# electric_fence.net
KiCad netlist of a schematic drawn in EAGLE
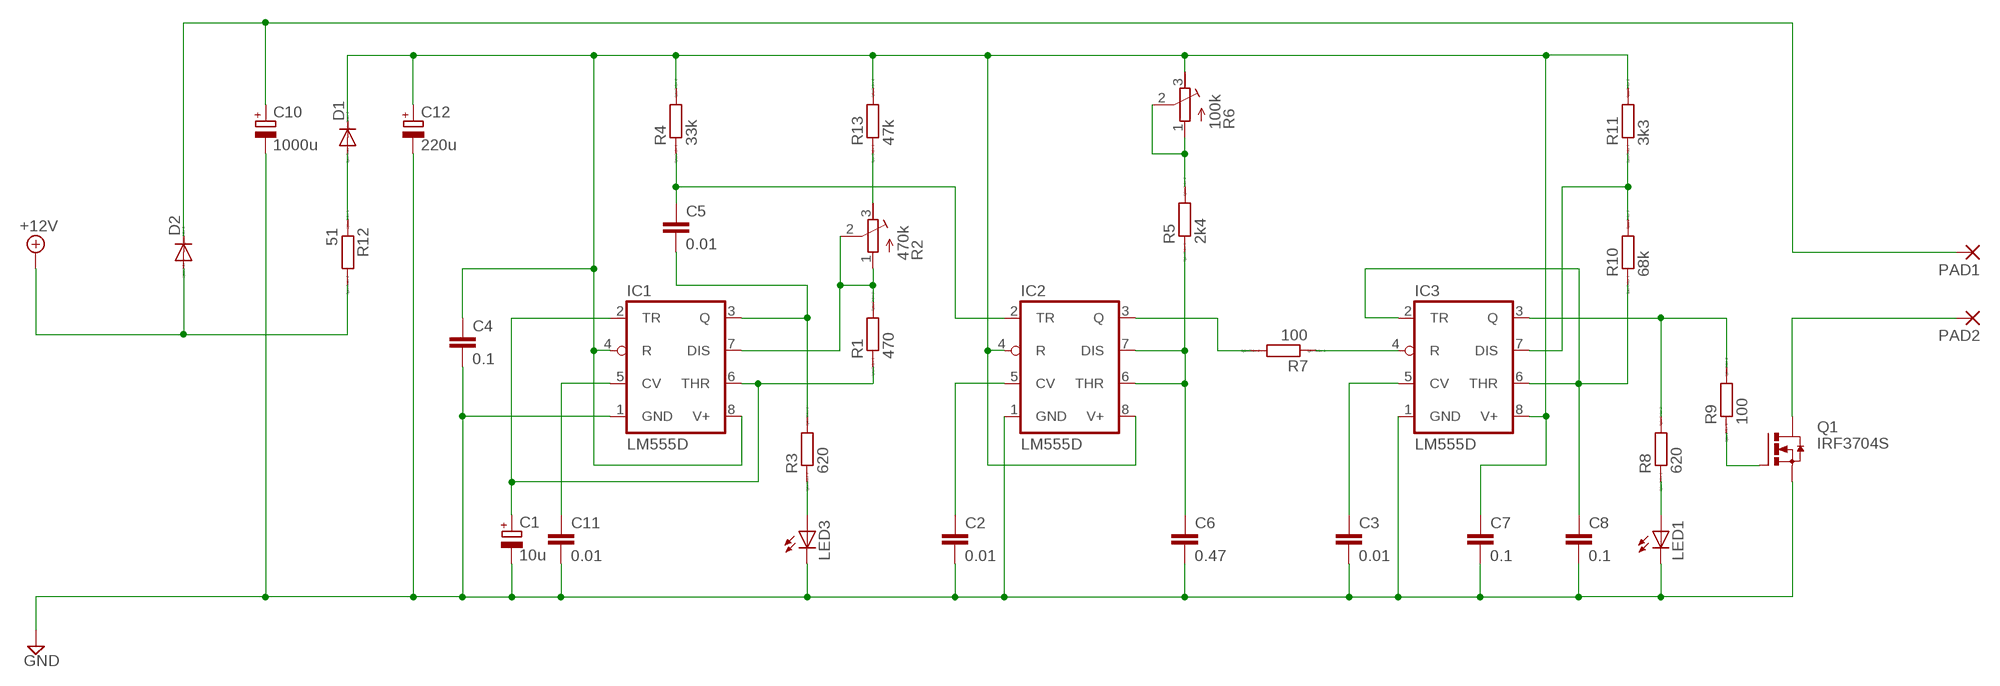
[diagram p0: schematic, sheet 1]

(export (version "E")
  (design (tool "Eeschema 10.0.6"))
  (components
    (comp (ref "C1")
      (value "10u")
      (footprint "eagle-import:E2-4")
      (libsource (lib "eagle-import") (part "CPOL-EUE2-4"))
    )
    (comp (ref "C2")
      (value "0.01")
      (footprint "eagle-import:C0402")
      (libsource (lib "eagle-import") (part "C-EUC0402"))
    )
    (comp (ref "C3")
      (value "0.01")
      (footprint "eagle-import:C0402")
      (libsource (lib "eagle-import") (part "C-EUC0402"))
    )
    (comp (ref "C4")
      (value "0.1")
      (footprint "eagle-import:C0402")
      (libsource (lib "eagle-import") (part "C-EUC0402"))
    )
    (comp (ref "C5")
      (value "0.01")
      (footprint "eagle-import:C0402")
      (libsource (lib "eagle-import") (part "C-EUC0402"))
    )
    (comp (ref "C6")
      (value "0.47")
      (footprint "eagle-import:C0402")
      (libsource (lib "eagle-import") (part "C-EUC0402"))
    )
    (comp (ref "C7")
      (value "0.1")
      (footprint "eagle-import:C0402")
      (libsource (lib "eagle-import") (part "C-EUC0402"))
    )
    (comp (ref "C8")
      (value "0.1")
      (footprint "eagle-import:C0402")
      (libsource (lib "eagle-import") (part "C-EUC0402"))
    )
    (comp (ref "C10")
      (value "1000u")
      (footprint "eagle-import:E2-4")
      (libsource (lib "eagle-import") (part "CPOL-EUE2-4"))
    )
    (comp (ref "C11")
      (value "0.01")
      (footprint "eagle-import:C0402")
      (libsource (lib "eagle-import") (part "C-EUC0402"))
    )
    (comp (ref "C12")
      (value "220u")
      (footprint "eagle-import:E2-4")
      (libsource (lib "eagle-import") (part "CPOL-EUE2-4"))
    )
    (comp (ref "D1")
      (value "DIODE-DO-214AC")
      (footprint "eagle-import:DO-214AC")
      (libsource (lib "eagle-import") (part "DIODE-DO-214AC"))
    )
    (comp (ref "D2")
      (value "DIODE-DO-214AC")
      (footprint "eagle-import:DO-214AC")
      (libsource (lib "eagle-import") (part "DIODE-DO-214AC"))
    )
    (comp (ref "IC1")
      (value "LM555D")
      (footprint "eagle-import:SO08")
      (libsource (lib "eagle-import") (part "555DLM"))
    )
    (comp (ref "IC2")
      (value "LM555D")
      (footprint "eagle-import:SO08")
      (libsource (lib "eagle-import") (part "555DLM"))
    )
    (comp (ref "IC3")
      (value "LM555D")
      (footprint "eagle-import:SO08")
      (libsource (lib "eagle-import") (part "555DLM"))
    )
    (comp (ref "LED1")
      (value "LEDCHIP-LED0805")
      (footprint "eagle-import:CHIP-LED0805")
      (libsource (lib "eagle-import") (part "LEDCHIP-LED0805"))
    )
    (comp (ref "LED3")
      (value "LEDCHIP-LED0805")
      (footprint "eagle-import:CHIP-LED0805")
      (libsource (lib "eagle-import") (part "LEDCHIP-LED0805"))
    )
    (comp (ref "PAD1")
      (value "SMD5")
      (footprint "eagle-import:SMD2,54-5,08")
      (libsource (lib "eagle-import") (part "SMD5"))
    )
    (comp (ref "PAD2")
      (value "SMD5")
      (footprint "eagle-import:SMD2,54-5,08")
      (libsource (lib "eagle-import") (part "SMD5"))
    )
    (comp (ref "Q1")
      (value "IRF3704S")
      (footprint "eagle-import:D2PACK")
      (libsource (lib "eagle-import") (part "IRF3704S"))
    )
    (comp (ref "R1")
      (value "470")
      (footprint "eagle-import:R0805")
      (libsource (lib "eagle-import") (part "R"))
    )
    (comp (ref "R2")
      (value "470k")
      (footprint "eagle-import:RTRIM4G_J")
      (libsource (lib "eagle-import") (part "R-TRIMM4G/J"))
    )
    (comp (ref "R3")
      (value "620")
      (footprint "eagle-import:R0805")
      (libsource (lib "eagle-import") (part "R"))
    )
    (comp (ref "R4")
      (value "33k")
      (footprint "eagle-import:R0805")
      (libsource (lib "eagle-import") (part "R"))
    )
    (comp (ref "R5")
      (value "2k4")
      (footprint "eagle-import:R0805")
      (libsource (lib "eagle-import") (part "R"))
    )
    (comp (ref "R6")
      (value "100k")
      (footprint "eagle-import:RTRIM4G_J")
      (libsource (lib "eagle-import") (part "R-TRIMM4G/J"))
    )
    (comp (ref "R7")
      (value "100")
      (footprint "eagle-import:R0805")
      (libsource (lib "eagle-import") (part "R"))
    )
    (comp (ref "R8")
      (value "620")
      (footprint "eagle-import:R0805")
      (libsource (lib "eagle-import") (part "R"))
    )
    (comp (ref "R9")
      (value "100")
      (footprint "eagle-import:R0805")
      (libsource (lib "eagle-import") (part "R"))
    )
    (comp (ref "R10")
      (value "68k")
      (footprint "eagle-import:R0805")
      (libsource (lib "eagle-import") (part "R"))
    )
    (comp (ref "R11")
      (value "3k3")
      (footprint "eagle-import:R0805")
      (libsource (lib "eagle-import") (part "R"))
    )
    (comp (ref "R12")
      (value "51")
      (footprint "eagle-import:R0805")
      (libsource (lib "eagle-import") (part "R"))
    )
    (comp (ref "R13")
      (value "47k")
      (footprint "eagle-import:R0805")
      (libsource (lib "eagle-import") (part "R"))
    )
  )
  (nets
    (net (code "1") (name "+12V") (class "Default")
      (node (ref "D2") (pin "A") (pinfunction "A_A") (pintype "passive"))
      (node (ref "R12") (pin "2") (pinfunction "2_2") (pintype "passive"))
    )
    (net (code "2") (name "GND") (class "Default")
      (node (ref "C1") (pin "-") (pinfunction "-_-") (pintype "passive"))
      (node (ref "C10") (pin "-") (pinfunction "-_-") (pintype "passive"))
      (node (ref "C11") (pin "2") (pinfunction "2_2") (pintype "passive"))
      (node (ref "C12") (pin "-") (pinfunction "-_-") (pintype "passive"))
      (node (ref "C2") (pin "2") (pinfunction "2_2") (pintype "passive"))
      (node (ref "C3") (pin "2") (pinfunction "2_2") (pintype "passive"))
      (node (ref "C4") (pin "2") (pinfunction "2_2") (pintype "passive"))
      (node (ref "C6") (pin "2") (pinfunction "2_2") (pintype "passive"))
      (node (ref "C7") (pin "2") (pinfunction "2_2") (pintype "passive"))
      (node (ref "C8") (pin "2") (pinfunction "2_2") (pintype "passive"))
      (node (ref "IC1") (pin "1") (pinfunction "GND_1") (pintype "power_in"))
      (node (ref "IC2") (pin "1") (pinfunction "GND_1") (pintype "power_in"))
      (node (ref "IC3") (pin "1") (pinfunction "GND_1") (pintype "power_in"))
      (node (ref "LED1") (pin "C") (pinfunction "C_C") (pintype "passive"))
      (node (ref "LED3") (pin "C") (pinfunction "C_C") (pintype "passive"))
      (node (ref "Q1") (pin "3") (pinfunction "S_3") (pintype "passive"))
    )
    (net (code "3") (name "Net-(D1-PadA)") (class "Default")
      (node (ref "D1") (pin "A") (pinfunction "A_A") (pintype "passive"))
      (node (ref "R12") (pin "1") (pinfunction "1_1") (pintype "passive"))
    )
    (net (code "4") (name "Net-(IC1-CV)") (class "Default")
      (node (ref "C11") (pin "1") (pinfunction "1_1") (pintype "passive"))
      (node (ref "IC1") (pin "5") (pinfunction "CV_5") (pintype "input"))
    )
    (net (code "5") (name "Net-(IC1-DIS)") (class "Default")
      (node (ref "IC1") (pin "7") (pinfunction "DIS_7") (pintype "input"))
      (node (ref "R1") (pin "2") (pinfunction "2_2") (pintype "passive"))
      (node (ref "R2") (pin "1") (pinfunction "A_1") (pintype "passive"))
      (node (ref "R2") (pin "2") (pinfunction "S_2") (pintype "passive"))
    )
    (net (code "6") (name "Net-(IC1-Q)") (class "Default")
      (node (ref "C5") (pin "2") (pinfunction "2_2") (pintype "passive"))
      (node (ref "IC1") (pin "3") (pinfunction "Q_3") (pintype "output"))
      (node (ref "R3") (pin "2") (pinfunction "2_2") (pintype "passive"))
    )
    (net (code "7") (name "Net-(IC1-R)") (class "Default")
      (node (ref "C12") (pin "+") (pinfunction "+_+") (pintype "passive"))
      (node (ref "C4") (pin "1") (pinfunction "1_1") (pintype "passive"))
      (node (ref "C7") (pin "1") (pinfunction "1_1") (pintype "passive"))
      (node (ref "D1") (pin "C") (pinfunction "C_C") (pintype "passive"))
      (node (ref "IC1") (pin "4") (pinfunction "R_4") (pintype "input"))
      (node (ref "IC1") (pin "8") (pinfunction "V+_8") (pintype "power_in"))
      (node (ref "IC2") (pin "4") (pinfunction "R_4") (pintype "input"))
      (node (ref "IC2") (pin "8") (pinfunction "V+_8") (pintype "power_in"))
      (node (ref "IC3") (pin "8") (pinfunction "V+_8") (pintype "power_in"))
      (node (ref "R11") (pin "2") (pinfunction "2_2") (pintype "passive"))
      (node (ref "R13") (pin "2") (pinfunction "2_2") (pintype "passive"))
      (node (ref "R4") (pin "2") (pinfunction "2_2") (pintype "passive"))
      (node (ref "R6") (pin "3") (pinfunction "E_3") (pintype "passive"))
    )
    (net (code "8") (name "Net-(IC1-THR)") (class "Default")
      (node (ref "C1") (pin "+") (pinfunction "+_+") (pintype "passive"))
      (node (ref "IC1") (pin "2") (pinfunction "TR_2") (pintype "input"))
      (node (ref "IC1") (pin "6") (pinfunction "THR_6") (pintype "input"))
      (node (ref "R1") (pin "1") (pinfunction "1_1") (pintype "passive"))
    )
    (net (code "9") (name "Net-(IC2-CV)") (class "Default")
      (node (ref "C2") (pin "1") (pinfunction "1_1") (pintype "passive"))
      (node (ref "IC2") (pin "5") (pinfunction "CV_5") (pintype "input"))
    )
    (net (code "10") (name "Net-(IC2-DIS)") (class "Default")
      (node (ref "C6") (pin "1") (pinfunction "1_1") (pintype "passive"))
      (node (ref "IC2") (pin "6") (pinfunction "THR_6") (pintype "input"))
      (node (ref "IC2") (pin "7") (pinfunction "DIS_7") (pintype "input"))
      (node (ref "R5") (pin "1") (pinfunction "1_1") (pintype "passive"))
    )
    (net (code "11") (name "Net-(IC2-Q)") (class "Default")
      (node (ref "IC2") (pin "3") (pinfunction "Q_3") (pintype "output"))
      (node (ref "R7") (pin "2") (pinfunction "2_2") (pintype "passive"))
    )
    (net (code "12") (name "Net-(IC2-TR)") (class "Default")
      (node (ref "C5") (pin "1") (pinfunction "1_1") (pintype "passive"))
      (node (ref "IC2") (pin "2") (pinfunction "TR_2") (pintype "input"))
      (node (ref "R4") (pin "1") (pinfunction "1_1") (pintype "passive"))
    )
    (net (code "13") (name "Net-(IC3-CV)") (class "Default")
      (node (ref "C3") (pin "1") (pinfunction "1_1") (pintype "passive"))
      (node (ref "IC3") (pin "5") (pinfunction "CV_5") (pintype "input"))
    )
    (net (code "14") (name "Net-(IC3-DIS)") (class "Default")
      (node (ref "IC3") (pin "7") (pinfunction "DIS_7") (pintype "input"))
      (node (ref "R10") (pin "2") (pinfunction "2_2") (pintype "passive"))
      (node (ref "R11") (pin "1") (pinfunction "1_1") (pintype "passive"))
    )
    (net (code "15") (name "Net-(IC3-Q)") (class "Default")
      (node (ref "IC3") (pin "3") (pinfunction "Q_3") (pintype "output"))
      (node (ref "R8") (pin "2") (pinfunction "2_2") (pintype "passive"))
      (node (ref "R9") (pin "2") (pinfunction "2_2") (pintype "passive"))
    )
    (net (code "16") (name "Net-(IC3-R)") (class "Default")
      (node (ref "IC3") (pin "4") (pinfunction "R_4") (pintype "input"))
      (node (ref "R7") (pin "1") (pinfunction "1_1") (pintype "passive"))
    )
    (net (code "17") (name "Net-(IC3-THR)") (class "Default")
      (node (ref "C8") (pin "1") (pinfunction "1_1") (pintype "passive"))
      (node (ref "IC3") (pin "2") (pinfunction "TR_2") (pintype "input"))
      (node (ref "IC3") (pin "6") (pinfunction "THR_6") (pintype "input"))
      (node (ref "R10") (pin "1") (pinfunction "1_1") (pintype "passive"))
    )
    (net (code "18") (name "Net-(LED1-PadA)") (class "Default")
      (node (ref "LED1") (pin "A") (pinfunction "A_A") (pintype "passive"))
      (node (ref "R8") (pin "1") (pinfunction "1_1") (pintype "passive"))
    )
    (net (code "19") (name "Net-(LED3-PadA)") (class "Default")
      (node (ref "LED3") (pin "A") (pinfunction "A_A") (pintype "passive"))
      (node (ref "R3") (pin "1") (pinfunction "1_1") (pintype "passive"))
    )
    (net (code "20") (name "Net-(PAD1-P)") (class "Default")
      (node (ref "C10") (pin "+") (pinfunction "+_+") (pintype "passive"))
      (node (ref "D2") (pin "C") (pinfunction "C_C") (pintype "passive"))
      (node (ref "PAD1") (pin "1") (pinfunction "P_1") (pintype "passive"))
    )
    (net (code "21") (name "Net-(PAD2-P)") (class "Default")
      (node (ref "PAD2") (pin "1") (pinfunction "P_1") (pintype "passive"))
      (node (ref "Q1") (pin "2") (pinfunction "D_2") (pintype "passive"))
    )
    (net (code "22") (name "Net-(Q1-G)") (class "Default")
      (node (ref "Q1") (pin "1") (pinfunction "G_1") (pintype "passive"))
      (node (ref "R9") (pin "1") (pinfunction "1_1") (pintype "passive"))
    )
    (net (code "23") (name "Net-(R2-E)") (class "Default")
      (node (ref "R13") (pin "1") (pinfunction "1_1") (pintype "passive"))
      (node (ref "R2") (pin "3") (pinfunction "E_3") (pintype "passive"))
    )
    (net (code "24") (name "Net-(R6-A)") (class "Default")
      (node (ref "R5") (pin "2") (pinfunction "2_2") (pintype "passive"))
      (node (ref "R6") (pin "1") (pinfunction "A_1") (pintype "passive"))
      (node (ref "R6") (pin "2") (pinfunction "S_2") (pintype "passive"))
    )
  )
)
